# 0456_pdm_pic_sch.net
KiCad netlist of a schematic drawn in EAGLE
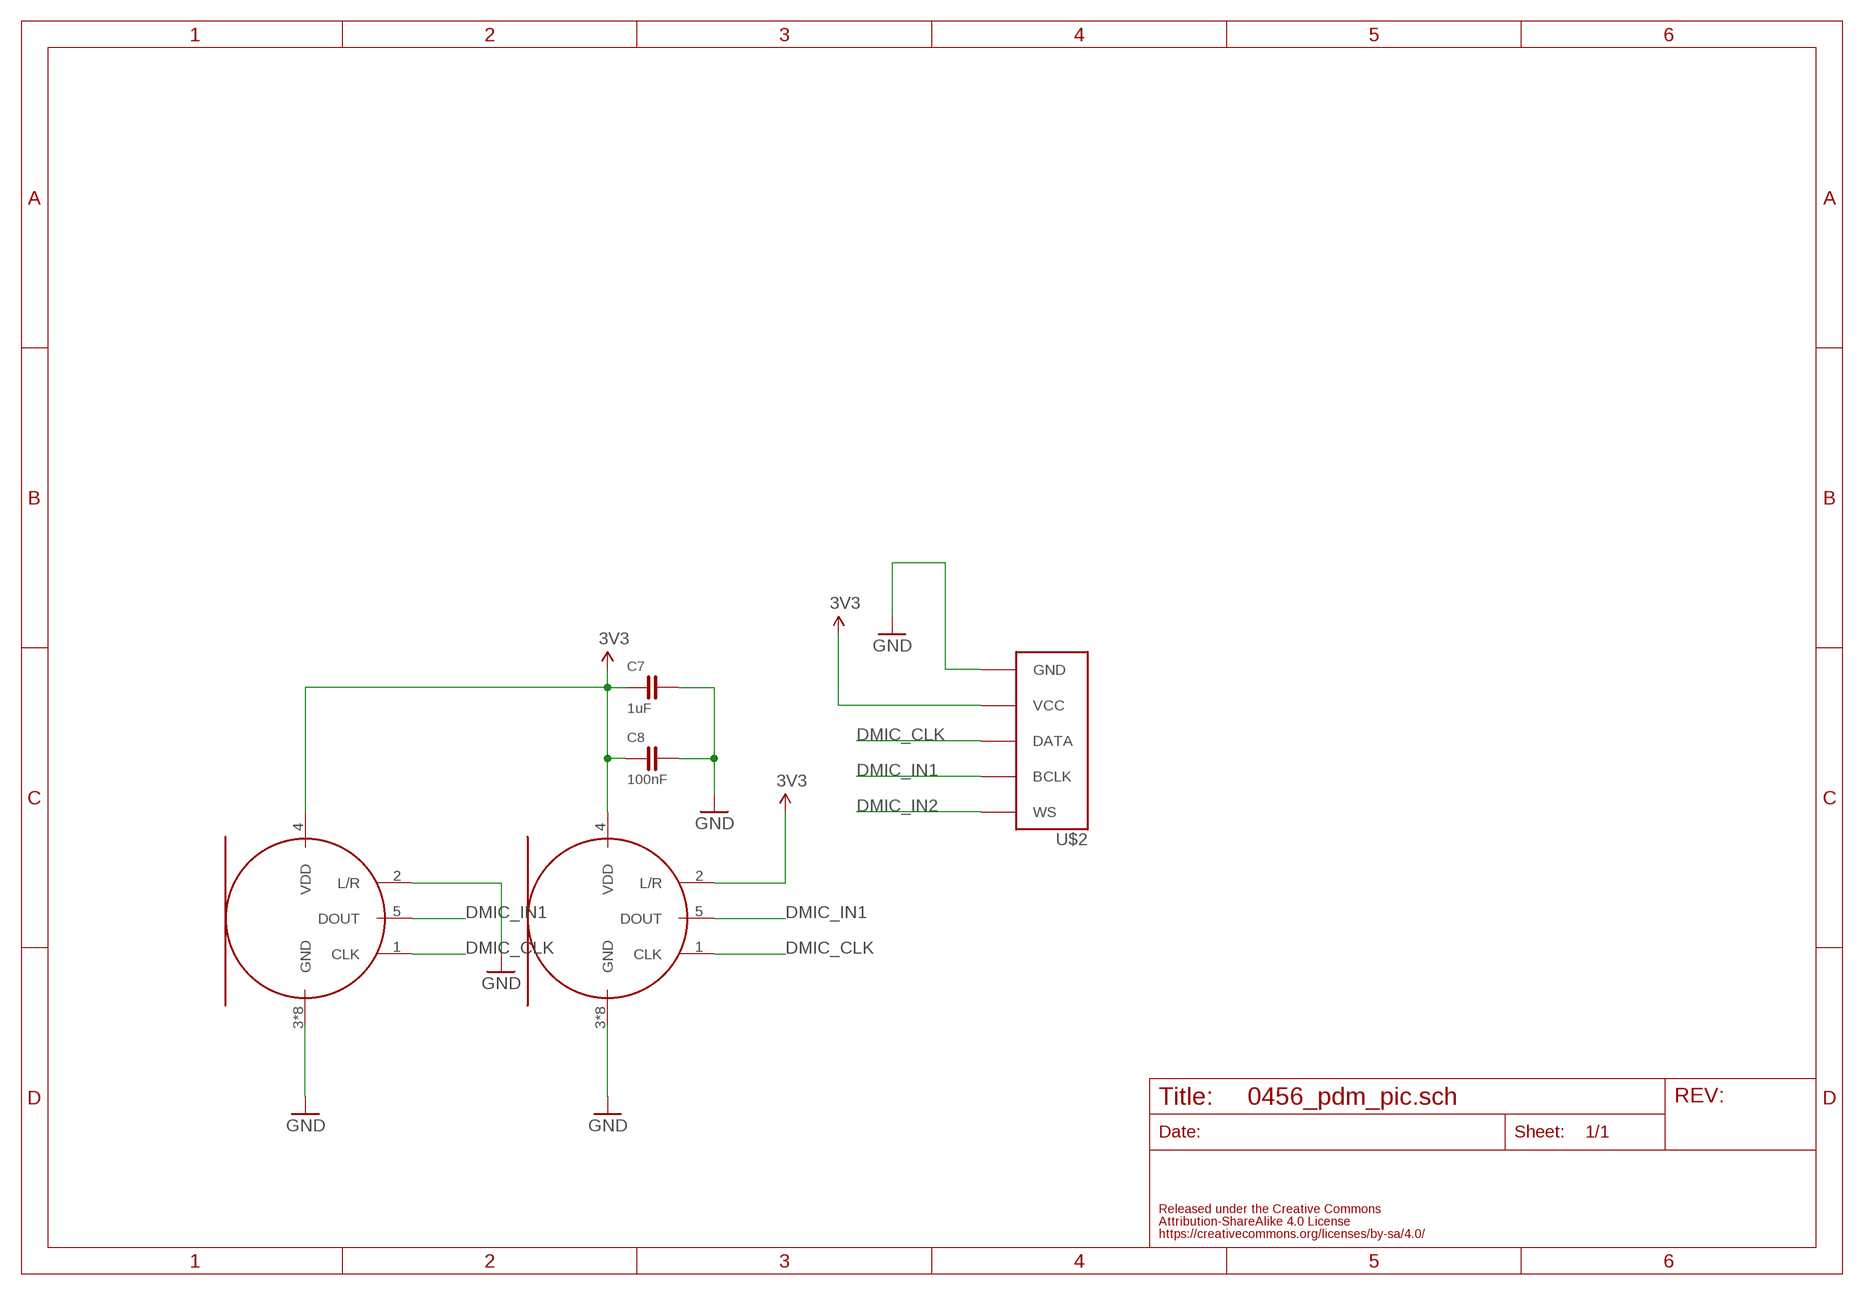
[diagram p0: schematic, sheet 1]

(export (version "E")
  (design (tool "Eeschema 10.0.6"))
  (components
    (comp (ref "C7")
      (value "1uF")
      (footprint "eagle-import:0603")
      (libsource (lib "eagle-import") (part "CAPACITOR-0603"))
    )
    (comp (ref "C8")
      (value "100nF")
      (footprint "eagle-import:0603")
      (libsource (lib "eagle-import") (part "CAPACITOR-0603"))
    )
    (comp (ref "LEFT")
      (value "PDM_MIC-INMP621")
      (footprint "eagle-import:INMP621")
      (libsource (lib "eagle-import") (part "PDM_MIC-INMP621"))
    )
    (comp (ref "RIGHT")
      (value "PDM_MIC-INMP621")
      (footprint "eagle-import:INMP621")
      (libsource (lib "eagle-import") (part "PDM_MIC-INMP621"))
    )
    (comp (ref "U$2")
      (value "FABO_BRICK_I2SLONG_BOTTOM")
      (footprint "eagle-import:FABO_BRICK_I2S_S05B-PASK-2_LONG_BOTTOM")
      (libsource (lib "eagle-import") (part "FABO_BRICK_I2SLONG_BOTTOM"))
    )
  )
  (nets
    (net (code "1") (name "/DMIC_CLK") (class "Default")
      (node (ref "LEFT") (pin "1") (pinfunction "CLK_1") (pintype "bidirectional"))
      (node (ref "RIGHT") (pin "1") (pinfunction "CLK_1") (pintype "bidirectional"))
      (node (ref "U$2") (pin "DATA") (pinfunction "DATA_DATA") (pintype "bidirectional"))
    )
    (net (code "2") (name "/DMIC_IN1") (class "Default")
      (node (ref "LEFT") (pin "5") (pinfunction "DOUT_5") (pintype "bidirectional"))
      (node (ref "RIGHT") (pin "5") (pinfunction "DOUT_5") (pintype "bidirectional"))
      (node (ref "U$2") (pin "BCLK") (pinfunction "BCLK_BCLK") (pintype "bidirectional"))
    )
    (net (code "3") (name "/DMIC_IN2") (class "Default")
      (node (ref "U$2") (pin "WS") (pinfunction "WS_WS") (pintype "bidirectional"))
    )
    (net (code "4") (name "3V3") (class "Default")
      (node (ref "C7") (pin "1") (pinfunction "1_1") (pintype "passive"))
      (node (ref "C8") (pin "1") (pinfunction "1_1") (pintype "passive"))
      (node (ref "LEFT") (pin "4") (pinfunction "VDD_4") (pintype "bidirectional"))
      (node (ref "RIGHT") (pin "2") (pinfunction "L/R_2") (pintype "bidirectional"))
      (node (ref "RIGHT") (pin "4") (pinfunction "VDD_4") (pintype "bidirectional"))
      (node (ref "U$2") (pin "VCC") (pinfunction "VCC_VCC") (pintype "bidirectional"))
    )
    (net (code "5") (name "GND") (class "Default")
      (node (ref "C7") (pin "2") (pinfunction "2_2") (pintype "passive"))
      (node (ref "C8") (pin "2") (pinfunction "2_2") (pintype "passive"))
      (node (ref "LEFT") (pin "10") (pinfunction "GND_10") (pintype "bidirectional"))
      (node (ref "LEFT") (pin "11") (pinfunction "GND_11") (pintype "bidirectional"))
      (node (ref "LEFT") (pin "12") (pinfunction "GND_12") (pintype "bidirectional"))
      (node (ref "LEFT") (pin "2") (pinfunction "L/R_2") (pintype "bidirectional"))
      (node (ref "LEFT") (pin "3") (pinfunction "GND_3") (pintype "bidirectional"))
      (node (ref "LEFT") (pin "6") (pinfunction "GND_6") (pintype "bidirectional"))
      (node (ref "LEFT") (pin "7") (pinfunction "GND_7") (pintype "bidirectional"))
      (node (ref "LEFT") (pin "8") (pinfunction "GND_8") (pintype "bidirectional"))
      (node (ref "LEFT") (pin "9") (pinfunction "GND_9") (pintype "bidirectional"))
      (node (ref "RIGHT") (pin "10") (pinfunction "GND_10") (pintype "bidirectional"))
      (node (ref "RIGHT") (pin "11") (pinfunction "GND_11") (pintype "bidirectional"))
      (node (ref "RIGHT") (pin "12") (pinfunction "GND_12") (pintype "bidirectional"))
      (node (ref "RIGHT") (pin "3") (pinfunction "GND_3") (pintype "bidirectional"))
      (node (ref "RIGHT") (pin "6") (pinfunction "GND_6") (pintype "bidirectional"))
      (node (ref "RIGHT") (pin "7") (pinfunction "GND_7") (pintype "bidirectional"))
      (node (ref "RIGHT") (pin "8") (pinfunction "GND_8") (pintype "bidirectional"))
      (node (ref "RIGHT") (pin "9") (pinfunction "GND_9") (pintype "bidirectional"))
      (node (ref "U$2") (pin "GND") (pinfunction "GND_GND") (pintype "bidirectional"))
    )
  )
)
